# CPU_DIN_mainboard.net
KiCad netlist of a schematic drawn in Altium Designer
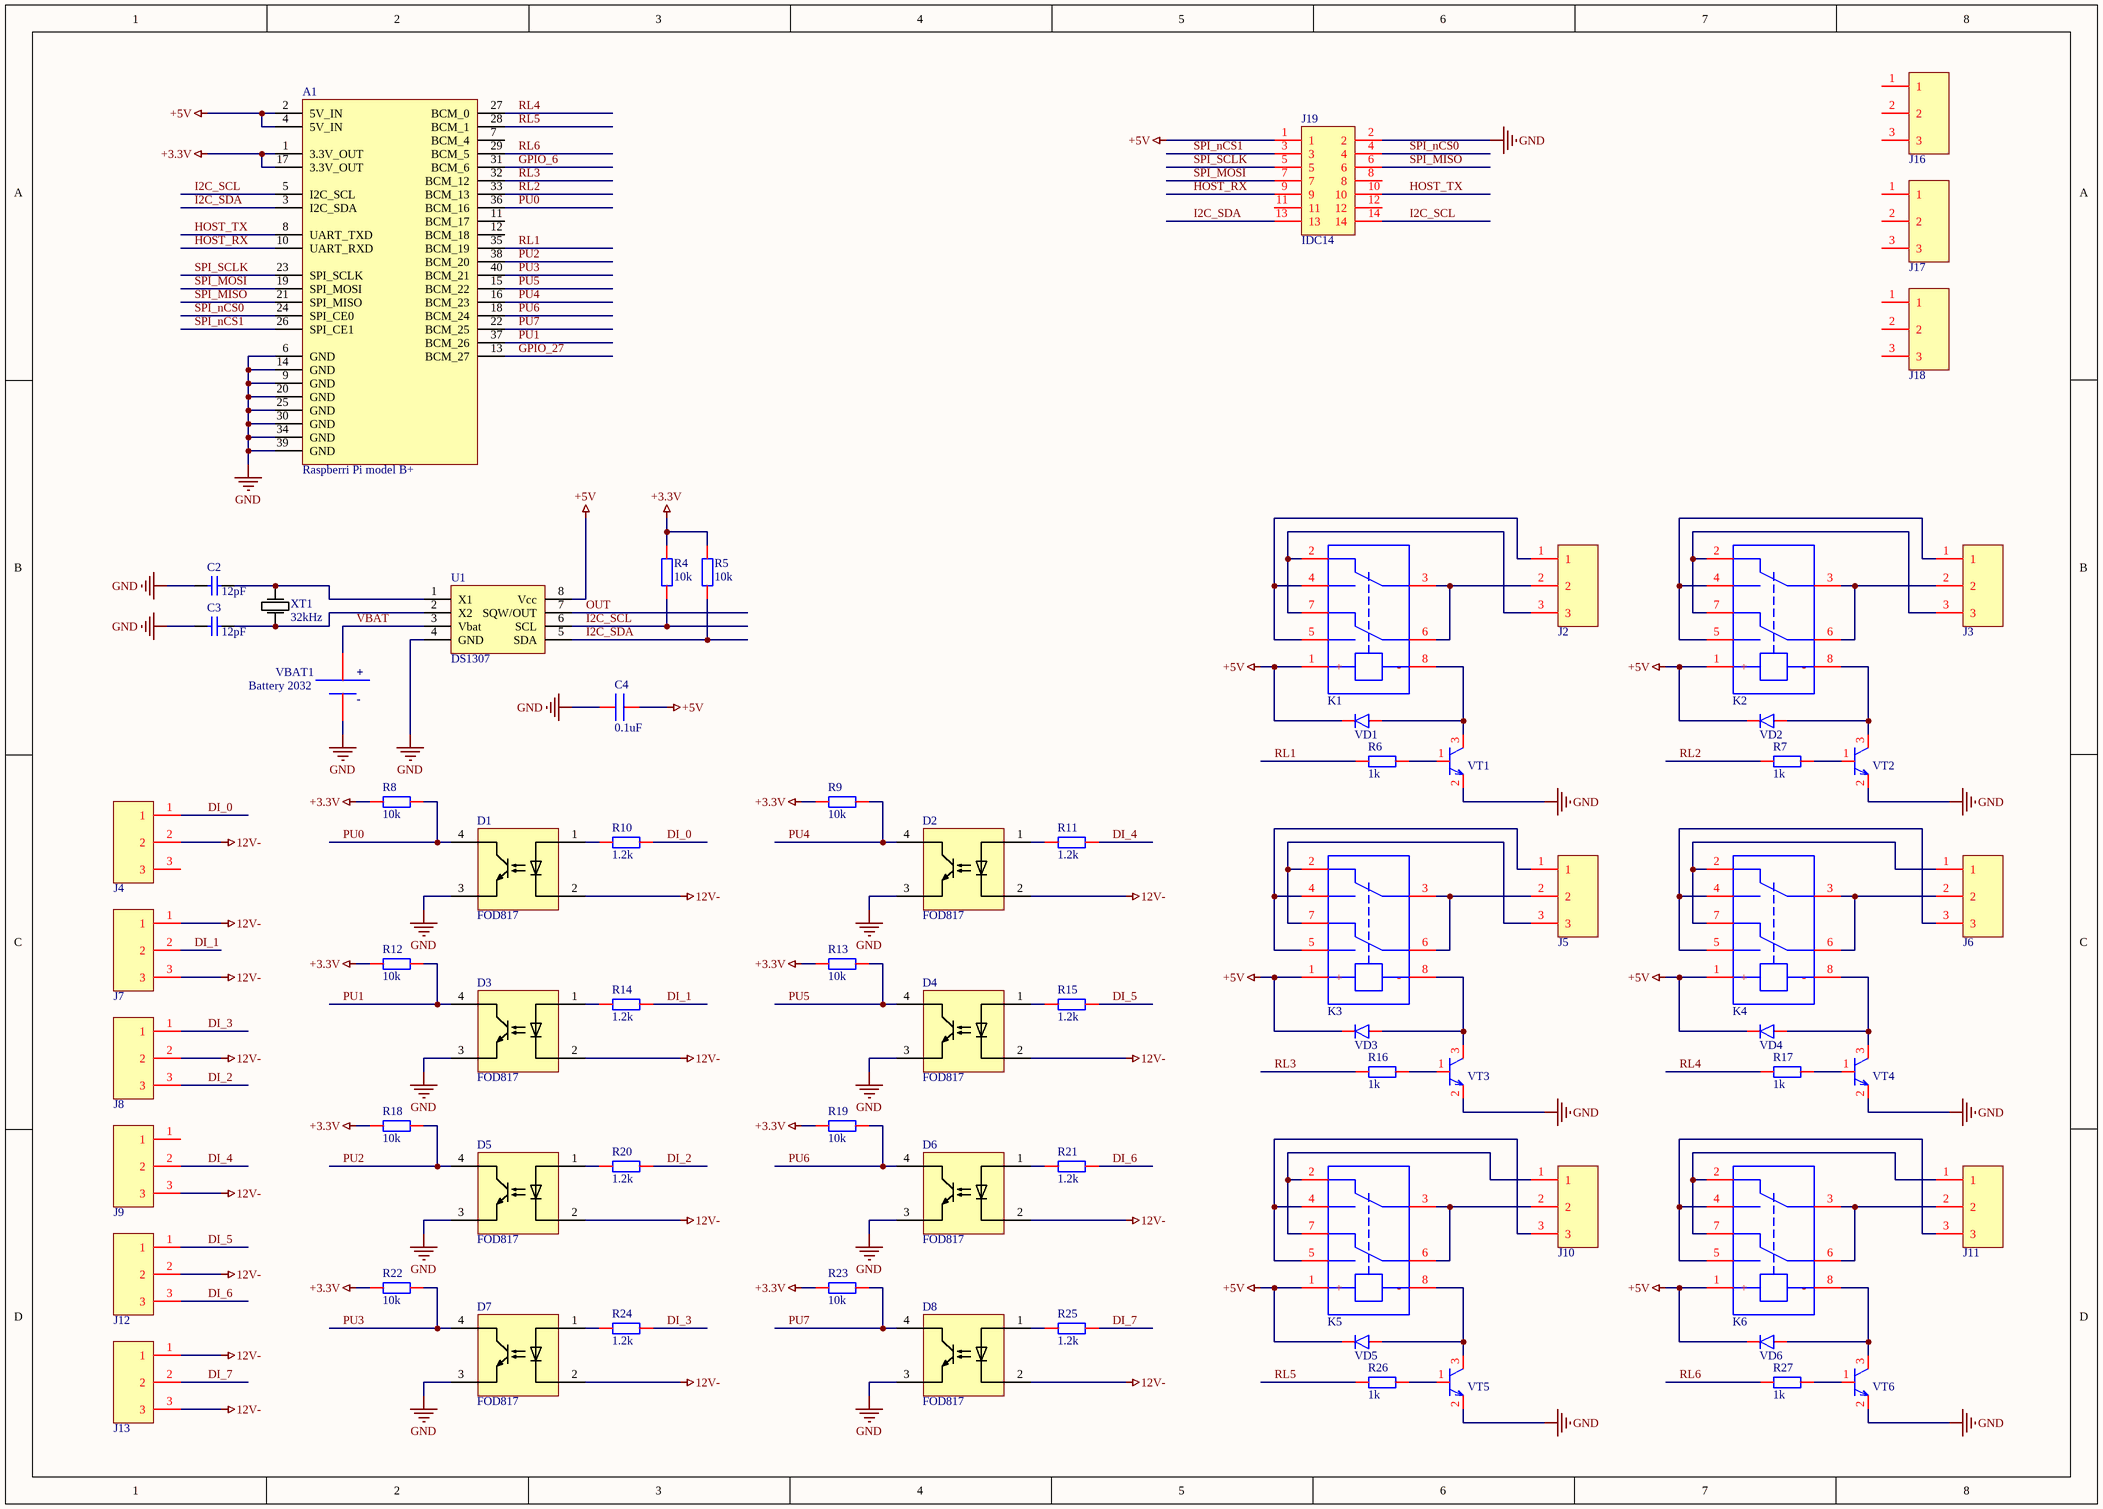
[diagram p0: CPU_DIN_mainboard.SchDoc]

(export (version "E")
  (design (tool "Eeschema 10.0.6"))
  (components
    (comp (ref "A1")
      (value "Raspberri Pi model B+")
      (footprint "PBD-40")
      (fields (field (name "PARTNUM") "PBD-40"))
      (libsource (lib "Lib_001") (part "RPi_Bplus"))
    )
    (comp (ref "C2") (value "12pF") (footprint "C0805") (libsource (lib "") (part "CAP_SMD_1")))
    (comp (ref "C3") (value "12pF") (footprint "C0805") (libsource (lib "") (part "CAP_SMD_1")))
    (comp (ref "C4") (value "0.1uF") (footprint "C0805") (libsource (lib "Lib_001") (part "CAP_SMD")))
    (comp (ref "D1")
      (value "FOD817")
      (footprint "DIP4_300mil_SMD")
      (fields (field (name "PARTNUM") "FOD817ASD"))
      (libsource (lib "Lib_001") (part "FOD817"))
    )
    (comp (ref "D2")
      (value "FOD817")
      (footprint "DIP4_300mil_SMD")
      (fields (field (name "PARTNUM") "FOD817ASD"))
      (libsource (lib "Lib_001") (part "FOD817"))
    )
    (comp (ref "D3")
      (value "FOD817")
      (footprint "DIP4_300mil_SMD")
      (fields (field (name "PARTNUM") "FOD817ASD"))
      (libsource (lib "Lib_001") (part "FOD817"))
    )
    (comp (ref "D4")
      (value "FOD817")
      (footprint "DIP4_300mil_SMD")
      (fields (field (name "PARTNUM") "FOD817ASD"))
      (libsource (lib "Lib_001") (part "FOD817"))
    )
    (comp (ref "D5")
      (value "FOD817")
      (footprint "DIP4_300mil_SMD")
      (fields (field (name "PARTNUM") "FOD817ASD"))
      (libsource (lib "Lib_001") (part "FOD817"))
    )
    (comp (ref "D6")
      (value "FOD817")
      (footprint "DIP4_300mil_SMD")
      (fields (field (name "PARTNUM") "FOD817ASD"))
      (libsource (lib "Lib_001") (part "FOD817"))
    )
    (comp (ref "D7")
      (value "FOD817")
      (footprint "DIP4_300mil_SMD")
      (fields (field (name "PARTNUM") "FOD817ASD"))
      (libsource (lib "Lib_001") (part "FOD817"))
    )
    (comp (ref "D8")
      (value "FOD817")
      (footprint "DIP4_300mil_SMD")
      (fields (field (name "PARTNUM") "FOD817ASD"))
      (libsource (lib "Lib_001") (part "FOD817"))
    )
    (comp (ref "J2")
      (value "Terminal block TB-3")
      (footprint "TB-3_ser370")
      (libsource (lib "Lib_001") (part "TB-3"))
    )
    (comp (ref "J3")
      (value "Terminal block TB-3")
      (footprint "TB-3_ser370")
      (libsource (lib "Lib_001") (part "TB-3"))
    )
    (comp (ref "J4")
      (value "Terminal block TB-3")
      (footprint "TB-3_ser370")
      (libsource (lib "") (part "TB-3_1"))
    )
    (comp (ref "J5")
      (value "Terminal block TB-3")
      (footprint "TB-3_ser370")
      (libsource (lib "Lib_001") (part "TB-3"))
    )
    (comp (ref "J6")
      (value "Terminal block TB-3")
      (footprint "TB-3_ser370")
      (libsource (lib "Lib_001") (part "TB-3"))
    )
    (comp (ref "J7")
      (value "Terminal block TB-3")
      (footprint "TB-3_ser370")
      (libsource (lib "") (part "TB-3_1"))
    )
    (comp (ref "J8")
      (value "Terminal block TB-3")
      (footprint "TB-3_ser370")
      (libsource (lib "") (part "TB-3_1"))
    )
    (comp (ref "J9")
      (value "Terminal block TB-3")
      (footprint "TB-3_ser370")
      (libsource (lib "") (part "TB-3_1"))
    )
    (comp (ref "J10")
      (value "Terminal block TB-3")
      (footprint "TB-3_ser370")
      (libsource (lib "Lib_001") (part "TB-3"))
    )
    (comp (ref "J11")
      (value "Terminal block TB-3")
      (footprint "TB-3_ser370")
      (libsource (lib "Lib_001") (part "TB-3"))
    )
    (comp (ref "J12")
      (value "Terminal block TB-3")
      (footprint "TB-3_ser370")
      (libsource (lib "") (part "TB-3_1"))
    )
    (comp (ref "J13")
      (value "Terminal block TB-3")
      (footprint "TB-3_ser370")
      (libsource (lib "") (part "TB-3_1"))
    )
    (comp (ref "J16")
      (value "Terminal block TB-3")
      (footprint "TB-3_ser370")
      (libsource (lib "Lib_001") (part "TB-3"))
    )
    (comp (ref "J17")
      (value "Terminal block TB-3")
      (footprint "TB-3_ser370")
      (libsource (lib "Lib_001") (part "TB-3"))
    )
    (comp (ref "J18")
      (value "Terminal block TB-3")
      (footprint "TB-3_ser370")
      (libsource (lib "Lib_001") (part "TB-3"))
    )
    (comp (ref "J19") (value "IDC14") (footprint "IDC14") (libsource (lib "Lib_001") (part "IDC14")))
    (comp (ref "K1") (value "IM03GR") (footprint "TYCO_2C") (libsource (lib "Lib_001") (part "IM06GR")))
    (comp (ref "K2") (value "IM03GR") (footprint "TYCO_2C") (libsource (lib "Lib_001") (part "IM06GR")))
    (comp (ref "K3") (value "IM03GR") (footprint "TYCO_2C") (libsource (lib "Lib_001") (part "IM06GR")))
    (comp (ref "K4") (value "IM03GR") (footprint "TYCO_2C") (libsource (lib "Lib_001") (part "IM06GR")))
    (comp (ref "K5") (value "IM03GR") (footprint "TYCO_2C") (libsource (lib "Lib_001") (part "IM06GR")))
    (comp (ref "K6") (value "IM03GR") (footprint "TYCO_2C") (libsource (lib "Lib_001") (part "IM06GR")))
    (comp (ref "R4") (value "10k") (footprint "R0805") (libsource (lib "Lib_001") (part "RES_SMD")))
    (comp (ref "R5") (value "10k") (footprint "R0805") (libsource (lib "Lib_001") (part "RES_SMD")))
    (comp (ref "R6") (value "1k") (footprint "R0805") (libsource (lib "Lib_001") (part "RES_SMD")))
    (comp (ref "R7") (value "1k") (footprint "R0805") (libsource (lib "Lib_001") (part "RES_SMD")))
    (comp (ref "R8") (value "10k") (footprint "R0805") (libsource (lib "Lib_001") (part "RES_SMD")))
    (comp (ref "R9") (value "10k") (footprint "R0805") (libsource (lib "Lib_001") (part "RES_SMD")))
    (comp (ref "R10") (value "1.2k") (footprint "R0805") (libsource (lib "Lib_001") (part "RES_SMD")))
    (comp (ref "R11") (value "1.2k") (footprint "R0805") (libsource (lib "Lib_001") (part "RES_SMD")))
    (comp (ref "R12") (value "10k") (footprint "R0805") (libsource (lib "Lib_001") (part "RES_SMD")))
    (comp (ref "R13") (value "10k") (footprint "R0805") (libsource (lib "Lib_001") (part "RES_SMD")))
    (comp (ref "R14") (value "1.2k") (footprint "R0805") (libsource (lib "Lib_001") (part "RES_SMD")))
    (comp (ref "R15") (value "1.2k") (footprint "R0805") (libsource (lib "Lib_001") (part "RES_SMD")))
    (comp (ref "R16") (value "1k") (footprint "R0805") (libsource (lib "Lib_001") (part "RES_SMD")))
    (comp (ref "R17") (value "1k") (footprint "R0805") (libsource (lib "Lib_001") (part "RES_SMD")))
    (comp (ref "R18") (value "10k") (footprint "R0805") (libsource (lib "Lib_001") (part "RES_SMD")))
    (comp (ref "R19") (value "10k") (footprint "R0805") (libsource (lib "Lib_001") (part "RES_SMD")))
    (comp (ref "R20") (value "1.2k") (footprint "R0805") (libsource (lib "Lib_001") (part "RES_SMD")))
    (comp (ref "R21") (value "1.2k") (footprint "R0805") (libsource (lib "Lib_001") (part "RES_SMD")))
    (comp (ref "R22") (value "10k") (footprint "R0805") (libsource (lib "Lib_001") (part "RES_SMD")))
    (comp (ref "R23") (value "10k") (footprint "R0805") (libsource (lib "Lib_001") (part "RES_SMD")))
    (comp (ref "R24") (value "1.2k") (footprint "R0805") (libsource (lib "Lib_001") (part "RES_SMD")))
    (comp (ref "R25") (value "1.2k") (footprint "R0805") (libsource (lib "Lib_001") (part "RES_SMD")))
    (comp (ref "R26") (value "1k") (footprint "R0805") (libsource (lib "Lib_001") (part "RES_SMD")))
    (comp (ref "R27") (value "1k") (footprint "R0805") (libsource (lib "Lib_001") (part "RES_SMD")))
    (comp (ref "U1")
      (value "DS1307")
      (footprint "SO-8_LM358D")
      (fields (field (name "PARTNUM") "DS1307Z+"))
      (libsource (lib "Lib_001") (part "DS1307"))
    )
    (comp (ref "VBAT1")
      (value "Battery 2032")
      (footprint "Battery_CR2032")
      (fields (field (name "PARTNUM") "BAT/HOLD.HU2032-LF"))
      (libsource (lib "Lib_001") (part "BATTERY_2032"))
    )
    (comp (ref "VD1")
      (value "BAV199")
      (footprint "SMA DIOD")
      (fields (field (name "PARTNUM") "VS-15MQ040NTRPBF"))
      (libsource (lib "Lib_001") (part "DIOD"))
    )
    (comp (ref "VD2")
      (value "BAV199")
      (footprint "SMA DIOD")
      (fields (field (name "PARTNUM") "VS-15MQ040NTRPBF"))
      (libsource (lib "Lib_001") (part "DIOD"))
    )
    (comp (ref "VD3")
      (value "BAV199")
      (footprint "SMA DIOD")
      (fields (field (name "PARTNUM") "VS-15MQ040NTRPBF"))
      (libsource (lib "Lib_001") (part "DIOD"))
    )
    (comp (ref "VD4")
      (value "BAV199")
      (footprint "SMA DIOD")
      (fields (field (name "PARTNUM") "VS-15MQ040NTRPBF"))
      (libsource (lib "Lib_001") (part "DIOD"))
    )
    (comp (ref "VD5")
      (value "BAV199")
      (footprint "SMA DIOD")
      (fields (field (name "PARTNUM") "VS-15MQ040NTRPBF"))
      (libsource (lib "Lib_001") (part "DIOD"))
    )
    (comp (ref "VD6")
      (value "BAV199")
      (footprint "SMA DIOD")
      (fields (field (name "PARTNUM") "VS-15MQ040NTRPBF"))
      (libsource (lib "Lib_001") (part "DIOD"))
    )
    (comp (ref "VT1")
      (value "BC817")
      (footprint "SOT23")
      (fields (field (name "PARTNUM") "BC817-16LT1G"))
      (libsource (lib "Lib_001") (part "BC817"))
    )
    (comp (ref "VT2")
      (value "BC817")
      (footprint "SOT23")
      (fields (field (name "PARTNUM") "BC817-16LT1G"))
      (libsource (lib "Lib_001") (part "BC817"))
    )
    (comp (ref "VT3")
      (value "BC817")
      (footprint "SOT23")
      (fields (field (name "PARTNUM") "BC817-16LT1G"))
      (libsource (lib "Lib_001") (part "BC817"))
    )
    (comp (ref "VT4")
      (value "BC817")
      (footprint "SOT23")
      (fields (field (name "PARTNUM") "BC817-16LT1G"))
      (libsource (lib "Lib_001") (part "BC817"))
    )
    (comp (ref "VT5")
      (value "BC817")
      (footprint "SOT23")
      (fields (field (name "PARTNUM") "BC817-16LT1G"))
      (libsource (lib "Lib_001") (part "BC817"))
    )
    (comp (ref "VT6")
      (value "BC817")
      (footprint "SOT23")
      (fields (field (name "PARTNUM") "BC817-16LT1G"))
      (libsource (lib "Lib_001") (part "BC817"))
    )
    (comp (ref "XT1")
      (value "32kHz")
      (footprint "XTAL_d2x6mm")
      (fields (field (name "PARTNUM") "KX-26T 32.768 kHz"))
      (libsource (lib "Lib_001") (part "XTAL"))
    )
  )
  (nets
    (net (code "1") (name "+3.3V") (class "Default")
      (node (ref "A1") (pin "1") (pinfunction "3.3V_OUT_1") (pintype "passive"))
      (node (ref "A1") (pin "17") (pinfunction "3.3V_OUT_17") (pintype "passive"))
      (node (ref "R12") (pin "2") (pinfunction "2_2") (pintype "passive"))
      (node (ref "R13") (pin "2") (pinfunction "2_2") (pintype "passive"))
      (node (ref "R18") (pin "2") (pinfunction "2_2") (pintype "passive"))
      (node (ref "R19") (pin "2") (pinfunction "2_2") (pintype "passive"))
      (node (ref "R22") (pin "2") (pinfunction "2_2") (pintype "passive"))
      (node (ref "R23") (pin "2") (pinfunction "2_2") (pintype "passive"))
      (node (ref "R4") (pin "2") (pinfunction "2_2") (pintype "passive"))
      (node (ref "R5") (pin "2") (pinfunction "2_2") (pintype "passive"))
      (node (ref "R8") (pin "2") (pinfunction "2_2") (pintype "passive"))
      (node (ref "R9") (pin "2") (pinfunction "2_2") (pintype "passive"))
    )
    (net (code "2") (name "+5V") (class "Default")
      (node (ref "A1") (pin "2") (pinfunction "5V_IN_2") (pintype "passive"))
      (node (ref "A1") (pin "4") (pinfunction "5V_IN_4") (pintype "passive"))
      (node (ref "C4") (pin "2") (pinfunction "2_2") (pintype "passive"))
      (node (ref "J19") (pin "1") (pinfunction "1_1") (pintype "passive"))
      (node (ref "K1") (pin "1") (pinfunction "+_1") (pintype "passive"))
      (node (ref "K2") (pin "1") (pinfunction "+_1") (pintype "passive"))
      (node (ref "K3") (pin "1") (pinfunction "+_1") (pintype "passive"))
      (node (ref "K4") (pin "1") (pinfunction "+_1") (pintype "passive"))
      (node (ref "K5") (pin "1") (pinfunction "+_1") (pintype "passive"))
      (node (ref "K6") (pin "1") (pinfunction "+_1") (pintype "passive"))
      (node (ref "U1") (pin "8") (pinfunction "Vcc_8") (pintype "passive"))
      (node (ref "VD1") (pin "K") (pinfunction "K_K") (pintype "passive"))
      (node (ref "VD2") (pin "K") (pinfunction "K_K") (pintype "passive"))
      (node (ref "VD3") (pin "K") (pinfunction "K_K") (pintype "passive"))
      (node (ref "VD4") (pin "K") (pinfunction "K_K") (pintype "passive"))
      (node (ref "VD5") (pin "K") (pinfunction "K_K") (pintype "passive"))
      (node (ref "VD6") (pin "K") (pinfunction "K_K") (pintype "passive"))
    )
    (net (code "3") (name "/DI_0") (class "Default")
      (node (ref "J4") (pin "1") (pinfunction "1_1") (pintype "passive"))
      (node (ref "R10") (pin "1") (pinfunction "1_1") (pintype "passive"))
    )
    (net (code "4") (name "/DI_1") (class "Default")
      (node (ref "J7") (pin "2") (pinfunction "2_2") (pintype "passive"))
      (node (ref "R14") (pin "1") (pinfunction "1_1") (pintype "passive"))
    )
    (net (code "5") (name "/DI_2") (class "Default")
      (node (ref "J8") (pin "3") (pinfunction "3_3") (pintype "passive"))
      (node (ref "R20") (pin "1") (pinfunction "1_1") (pintype "passive"))
    )
    (net (code "6") (name "/DI_3") (class "Default")
      (node (ref "J8") (pin "1") (pinfunction "1_1") (pintype "passive"))
      (node (ref "R24") (pin "1") (pinfunction "1_1") (pintype "passive"))
    )
    (net (code "7") (name "/DI_4") (class "Default")
      (node (ref "J9") (pin "2") (pinfunction "2_2") (pintype "passive"))
      (node (ref "R11") (pin "1") (pinfunction "1_1") (pintype "passive"))
    )
    (net (code "8") (name "/DI_5") (class "Default")
      (node (ref "J12") (pin "1") (pinfunction "1_1") (pintype "passive"))
      (node (ref "R15") (pin "1") (pinfunction "1_1") (pintype "passive"))
    )
    (net (code "9") (name "/DI_6") (class "Default")
      (node (ref "J12") (pin "3") (pinfunction "3_3") (pintype "passive"))
      (node (ref "R21") (pin "1") (pinfunction "1_1") (pintype "passive"))
    )
    (net (code "10") (name "/DI_7") (class "Default")
      (node (ref "J13") (pin "2") (pinfunction "2_2") (pintype "passive"))
      (node (ref "R25") (pin "1") (pinfunction "1_1") (pintype "passive"))
    )
    (net (code "11") (name "/GPIO_6") (class "Default")
      (node (ref "A1") (pin "31") (pinfunction "BCM_6_31") (pintype "passive"))
    )
    (net (code "12") (name "/GPIO_27") (class "Default")
      (node (ref "A1") (pin "13") (pinfunction "BCM_27_13") (pintype "passive"))
    )
    (net (code "13") (name "/HOST_RX") (class "Default")
      (node (ref "A1") (pin "10") (pinfunction "UART_RXD_10") (pintype "passive"))
      (node (ref "J19") (pin "9") (pinfunction "9_9") (pintype "passive"))
    )
    (net (code "14") (name "/HOST_TX") (class "Default")
      (node (ref "A1") (pin "8") (pinfunction "UART_TXD_8") (pintype "passive"))
      (node (ref "J19") (pin "10") (pinfunction "10_10") (pintype "passive"))
    )
    (net (code "15") (name "/I2C_SCL") (class "Default")
      (node (ref "A1") (pin "5") (pinfunction "I2C_SCL_5") (pintype "passive"))
      (node (ref "J19") (pin "14") (pinfunction "14_14") (pintype "passive"))
      (node (ref "R4") (pin "1") (pinfunction "1_1") (pintype "passive"))
      (node (ref "U1") (pin "6") (pinfunction "SCL_6") (pintype "passive"))
    )
    (net (code "16") (name "/I2C_SDA") (class "Default")
      (node (ref "A1") (pin "3") (pinfunction "I2C_SDA_3") (pintype "passive"))
      (node (ref "J19") (pin "13") (pinfunction "13_13") (pintype "passive"))
      (node (ref "R5") (pin "1") (pinfunction "1_1") (pintype "passive"))
      (node (ref "U1") (pin "5") (pinfunction "SDA_5") (pintype "passive"))
    )
    (net (code "17") (name "/OUT") (class "Default")
      (node (ref "U1") (pin "7") (pinfunction "SQW/OUT_7") (pintype "passive"))
    )
    (net (code "18") (name "/PU0") (class "Default")
      (node (ref "A1") (pin "36") (pinfunction "BCM_16_36") (pintype "passive"))
      (node (ref "D1") (pin "4") (pinfunction "4_4") (pintype "passive"))
      (node (ref "R8") (pin "1") (pinfunction "1_1") (pintype "passive"))
    )
    (net (code "19") (name "/PU1") (class "Default")
      (node (ref "A1") (pin "37") (pinfunction "BCM_26_37") (pintype "passive"))
      (node (ref "D3") (pin "4") (pinfunction "4_4") (pintype "passive"))
      (node (ref "R12") (pin "1") (pinfunction "1_1") (pintype "passive"))
    )
    (net (code "20") (name "/PU2") (class "Default")
      (node (ref "A1") (pin "38") (pinfunction "BCM_20_38") (pintype "passive"))
      (node (ref "D5") (pin "4") (pinfunction "4_4") (pintype "passive"))
      (node (ref "R18") (pin "1") (pinfunction "1_1") (pintype "passive"))
    )
    (net (code "21") (name "/PU3") (class "Default")
      (node (ref "A1") (pin "40") (pinfunction "BCM_21_40") (pintype "passive"))
      (node (ref "D7") (pin "4") (pinfunction "4_4") (pintype "passive"))
      (node (ref "R22") (pin "1") (pinfunction "1_1") (pintype "passive"))
    )
    (net (code "22") (name "/PU4") (class "Default")
      (node (ref "A1") (pin "16") (pinfunction "BCM_23_16") (pintype "passive"))
      (node (ref "D2") (pin "4") (pinfunction "4_4") (pintype "passive"))
      (node (ref "R9") (pin "1") (pinfunction "1_1") (pintype "passive"))
    )
    (net (code "23") (name "/PU5") (class "Default")
      (node (ref "A1") (pin "15") (pinfunction "BCM_22_15") (pintype "passive"))
      (node (ref "D4") (pin "4") (pinfunction "4_4") (pintype "passive"))
      (node (ref "R13") (pin "1") (pinfunction "1_1") (pintype "passive"))
    )
    (net (code "24") (name "/PU6") (class "Default")
      (node (ref "A1") (pin "18") (pinfunction "BCM_24_18") (pintype "passive"))
      (node (ref "D6") (pin "4") (pinfunction "4_4") (pintype "passive"))
      (node (ref "R19") (pin "1") (pinfunction "1_1") (pintype "passive"))
    )
    (net (code "25") (name "/PU7") (class "Default")
      (node (ref "A1") (pin "22") (pinfunction "BCM_25_22") (pintype "passive"))
      (node (ref "D8") (pin "4") (pinfunction "4_4") (pintype "passive"))
      (node (ref "R23") (pin "1") (pinfunction "1_1") (pintype "passive"))
    )
    (net (code "26") (name "/RL1") (class "Default")
      (node (ref "A1") (pin "35") (pinfunction "BCM_19_35") (pintype "passive"))
      (node (ref "R6") (pin "2") (pinfunction "2_2") (pintype "passive"))
    )
    (net (code "27") (name "/RL2") (class "Default")
      (node (ref "A1") (pin "33") (pinfunction "BCM_13_33") (pintype "passive"))
      (node (ref "R7") (pin "2") (pinfunction "2_2") (pintype "passive"))
    )
    (net (code "28") (name "/RL3") (class "Default")
      (node (ref "A1") (pin "32") (pinfunction "BCM_12_32") (pintype "passive"))
      (node (ref "R16") (pin "2") (pinfunction "2_2") (pintype "passive"))
    )
    (net (code "29") (name "/RL4") (class "Default")
      (node (ref "A1") (pin "27") (pinfunction "BCM_0_27") (pintype "passive"))
      (node (ref "R17") (pin "2") (pinfunction "2_2") (pintype "passive"))
    )
    (net (code "30") (name "/RL5") (class "Default")
      (node (ref "A1") (pin "28") (pinfunction "BCM_1_28") (pintype "passive"))
      (node (ref "R26") (pin "2") (pinfunction "2_2") (pintype "passive"))
    )
    (net (code "31") (name "/RL6") (class "Default")
      (node (ref "A1") (pin "29") (pinfunction "BCM_5_29") (pintype "passive"))
      (node (ref "R27") (pin "2") (pinfunction "2_2") (pintype "passive"))
    )
    (net (code "32") (name "/SPI_MISO") (class "Default")
      (node (ref "A1") (pin "21") (pinfunction "SPI_MISO_21") (pintype "passive"))
      (node (ref "J19") (pin "6") (pinfunction "6_6") (pintype "passive"))
    )
    (net (code "33") (name "/SPI_MOSI") (class "Default")
      (node (ref "A1") (pin "19") (pinfunction "SPI_MOSI_19") (pintype "passive"))
      (node (ref "J19") (pin "7") (pinfunction "7_7") (pintype "passive"))
    )
    (net (code "34") (name "/SPI_SCLK") (class "Default")
      (node (ref "A1") (pin "23") (pinfunction "SPI_SCLK_23") (pintype "passive"))
      (node (ref "J19") (pin "5") (pinfunction "5_5") (pintype "passive"))
    )
    (net (code "35") (name "/SPI_nCS0") (class "Default")
      (node (ref "A1") (pin "24") (pinfunction "SPI_CE0_24") (pintype "passive"))
      (node (ref "J19") (pin "4") (pinfunction "4_4") (pintype "passive"))
    )
    (net (code "36") (name "/SPI_nCS1") (class "Default")
      (node (ref "A1") (pin "26") (pinfunction "SPI_CE1_26") (pintype "passive"))
      (node (ref "J19") (pin "3") (pinfunction "3_3") (pintype "passive"))
    )
    (net (code "37") (name "/VBAT") (class "Default")
      (node (ref "U1") (pin "3") (pinfunction "Vbat_3") (pintype "passive"))
      (node (ref "VBAT1") (pin "P") (pinfunction "+_P") (pintype "passive"))
    )
    (net (code "38") (name "12V-") (class "Default")
      (node (ref "D1") (pin "2") (pinfunction "2_2") (pintype "passive"))
      (node (ref "D2") (pin "2") (pinfunction "2_2") (pintype "passive"))
      (node (ref "D3") (pin "2") (pinfunction "2_2") (pintype "passive"))
      (node (ref "D4") (pin "2") (pinfunction "2_2") (pintype "passive"))
      (node (ref "D5") (pin "2") (pinfunction "2_2") (pintype "passive"))
      (node (ref "D6") (pin "2") (pinfunction "2_2") (pintype "passive"))
      (node (ref "D7") (pin "2") (pinfunction "2_2") (pintype "passive"))
      (node (ref "D8") (pin "2") (pinfunction "2_2") (pintype "passive"))
      (node (ref "J12") (pin "2") (pinfunction "2_2") (pintype "passive"))
      (node (ref "J13") (pin "1") (pinfunction "1_1") (pintype "passive"))
      (node (ref "J13") (pin "3") (pinfunction "3_3") (pintype "passive"))
      (node (ref "J4") (pin "2") (pinfunction "2_2") (pintype "passive"))
      (node (ref "J7") (pin "1") (pinfunction "1_1") (pintype "passive"))
      (node (ref "J7") (pin "3") (pinfunction "3_3") (pintype "passive"))
      (node (ref "J8") (pin "2") (pinfunction "2_2") (pintype "passive"))
      (node (ref "J9") (pin "3") (pinfunction "3_3") (pintype "passive"))
    )
    (net (code "39") (name "GND") (class "Default")
      (node (ref "A1") (pin "14") (pinfunction "GND_14") (pintype "passive"))
      (node (ref "A1") (pin "20") (pinfunction "GND_20") (pintype "passive"))
      (node (ref "A1") (pin "25") (pinfunction "GND_25") (pintype "passive"))
      (node (ref "A1") (pin "30") (pinfunction "GND_30") (pintype "passive"))
      (node (ref "A1") (pin "34") (pinfunction "GND_34") (pintype "passive"))
      (node (ref "A1") (pin "39") (pinfunction "GND_39") (pintype "passive"))
      (node (ref "A1") (pin "6") (pinfunction "GND_6") (pintype "passive"))
      (node (ref "A1") (pin "9") (pinfunction "GND_9") (pintype "passive"))
      (node (ref "C2") (pin "2") (pinfunction "2_2") (pintype "passive"))
      (node (ref "C3") (pin "2") (pinfunction "2_2") (pintype "passive"))
      (node (ref "C4") (pin "1") (pinfunction "1_1") (pintype "passive"))
      (node (ref "D1") (pin "3") (pinfunction "3_3") (pintype "passive"))
      (node (ref "D2") (pin "3") (pinfunction "3_3") (pintype "passive"))
      (node (ref "D3") (pin "3") (pinfunction "3_3") (pintype "passive"))
      (node (ref "D4") (pin "3") (pinfunction "3_3") (pintype "passive"))
      (node (ref "D5") (pin "3") (pinfunction "3_3") (pintype "passive"))
      (node (ref "D6") (pin "3") (pinfunction "3_3") (pintype "passive"))
      (node (ref "D7") (pin "3") (pinfunction "3_3") (pintype "passive"))
      (node (ref "D8") (pin "3") (pinfunction "3_3") (pintype "passive"))
      (node (ref "J19") (pin "2") (pinfunction "2_2") (pintype "passive"))
      (node (ref "U1") (pin "4") (pinfunction "GND_4") (pintype "passive"))
      (node (ref "VBAT1") (pin "N") (pinfunction "-_N") (pintype "passive"))
      (node (ref "VT1") (pin "2") (pinfunction "E_2") (pintype "passive"))
      (node (ref "VT2") (pin "2") (pinfunction "E_2") (pintype "passive"))
      (node (ref "VT3") (pin "2") (pinfunction "E_2") (pintype "passive"))
      (node (ref "VT4") (pin "2") (pinfunction "E_2") (pintype "passive"))
      (node (ref "VT5") (pin "2") (pinfunction "E_2") (pintype "passive"))
      (node (ref "VT6") (pin "2") (pinfunction "E_2") (pintype "passive"))
    )
    (net (code "40") (name "Net-(D1-Pad1)") (class "Default")
      (node (ref "D1") (pin "1") (pinfunction "1_1") (pintype "passive"))
      (node (ref "R10") (pin "2") (pinfunction "2_2") (pintype "passive"))
    )
    (net (code "41") (name "Net-(D2-Pad1)") (class "Default")
      (node (ref "D2") (pin "1") (pinfunction "1_1") (pintype "passive"))
      (node (ref "R11") (pin "2") (pinfunction "2_2") (pintype "passive"))
    )
    (net (code "42") (name "Net-(D3-Pad1)") (class "Default")
      (node (ref "D3") (pin "1") (pinfunction "1_1") (pintype "passive"))
      (node (ref "R14") (pin "2") (pinfunction "2_2") (pintype "passive"))
    )
    (net (code "43") (name "Net-(D4-Pad1)") (class "Default")
      (node (ref "D4") (pin "1") (pinfunction "1_1") (pintype "passive"))
      (node (ref "R15") (pin "2") (pinfunction "2_2") (pintype "passive"))
    )
    (net (code "44") (name "Net-(D5-Pad1)") (class "Default")
      (node (ref "D5") (pin "1") (pinfunction "1_1") (pintype "passive"))
      (node (ref "R20") (pin "2") (pinfunction "2_2") (pintype "passive"))
    )
    (net (code "45") (name "Net-(D6-Pad1)") (class "Default")
      (node (ref "D6") (pin "1") (pinfunction "1_1") (pintype "passive"))
      (node (ref "R21") (pin "2") (pinfunction "2_2") (pintype "passive"))
    )
    (net (code "46") (name "Net-(D7-Pad1)") (class "Default")
      (node (ref "D7") (pin "1") (pinfunction "1_1") (pintype "passive"))
      (node (ref "R24") (pin "2") (pinfunction "2_2") (pintype "passive"))
    )
    (net (code "47") (name "Net-(D8-Pad1)") (class "Default")
      (node (ref "D8") (pin "1") (pinfunction "1_1") (pintype "passive"))
      (node (ref "R25") (pin "2") (pinfunction "2_2") (pintype "passive"))
    )
    (net (code "48") (name "Net-(J2-Pad1)") (class "Default")
      (node (ref "J2") (pin "1") (pinfunction "1_1") (pintype "passive"))
      (node (ref "K1") (pin "4") (pinfunction "4_4") (pintype "passive"))
      (node (ref "K1") (pin "5") (pinfunction "5_5") (pintype "passive"))
    )
    (net (code "49") (name "Net-(J2-Pad3)") (class "Default")
      (node (ref "J2") (pin "3") (pinfunction "3_3") (pintype "passive"))
      (node (ref "K1") (pin "2") (pinfunction "2_2") (pintype "passive"))
      (node (ref "K1") (pin "7") (pinfunction "7_7") (pintype "passive"))
    )
    (net (code "50") (name "Net-(J3-Pad1)") (class "Default")
      (node (ref "J3") (pin "1") (pinfunction "1_1") (pintype "passive"))
      (node (ref "K2") (pin "4") (pinfunction "4_4") (pintype "passive"))
      (node (ref "K2") (pin "5") (pinfunction "5_5") (pintype "passive"))
    )
    (net (code "51") (name "Net-(J3-Pad3)") (class "Default")
      (node (ref "J3") (pin "3") (pinfunction "3_3") (pintype "passive"))
      (node (ref "K2") (pin "2") (pinfunction "2_2") (pintype "passive"))
      (node (ref "K2") (pin "7") (pinfunction "7_7") (pintype "passive"))
    )
    (net (code "52") (name "Net-(J5-Pad1)") (class "Default")
      (node (ref "J5") (pin "1") (pinfunction "1_1") (pintype "passive"))
      (node (ref "K3") (pin "4") (pinfunction "4_4") (pintype "passive"))
      (node (ref "K3") (pin "5") (pinfunction "5_5") (pintype "passive"))
    )
    (net (code "53") (name "Net-(J5-Pad3)") (class "Default")
      (node (ref "J5") (pin "3") (pinfunction "3_3") (pintype "passive"))
      (node (ref "K3") (pin "2") (pinfunction "2_2") (pintype "passive"))
      (node (ref "K3") (pin "7") (pinfunction "7_7") (pintype "passive"))
    )
    (net (code "54") (name "Net-(J6-Pad1)") (class "Default")
      (node (ref "J6") (pin "1") (pinfunction "1_1") (pintype "passive"))
      (node (ref "K4") (pin "2") (pinfunction "2_2") (pintype "passive"))
      (node (ref "K4") (pin "7") (pinfunction "7_7") (pintype "passive"))
    )
    (net (code "55") (name "Net-(J6-Pad3)") (class "Default")
      (node (ref "J6") (pin "3") (pinfunction "3_3") (pintype "passive"))
      (node (ref "K4") (pin "4") (pinfunction "4_4") (pintype "passive"))
      (node (ref "K4") (pin "5") (pinfunction "5_5") (pintype "passive"))
    )
    (net (code "56") (name "Net-(J10-Pad1)") (class "Default")
      (node (ref "J10") (pin "1") (pinfunction "1_1") (pintype "passive"))
      (node (ref "K5") (pin "2") (pinfunction "2_2") (pintype "passive"))
      (node (ref "K5") (pin "7") (pinfunction "7_7") (pintype "passive"))
    )
    (net (code "57") (name "Net-(J10-Pad3)") (class "Default")
      (node (ref "J10") (pin "3") (pinfunction "3_3") (pintype "passive"))
      (node (ref "K5") (pin "4") (pinfunction "4_4") (pintype "passive"))
      (node (ref "K5") (pin "5") (pinfunction "5_5") (pintype "passive"))
    )
    (net (code "58") (name "Net-(J11-Pad1)") (class "Default")
      (node (ref "J11") (pin "1") (pinfunction "1_1") (pintype "passive"))
      (node (ref "K6") (pin "2") (pinfunction "2_2") (pintype "passive"))
      (node (ref "K6") (pin "7") (pinfunction "7_7") (pintype "passive"))
    )
    (net (code "59") (name "Net-(J11-Pad3)") (class "Default")
      (node (ref "J11") (pin "3") (pinfunction "3_3") (pintype "passive"))
      (node (ref "K6") (pin "4") (pinfunction "4_4") (pintype "passive"))
      (node (ref "K6") (pin "5") (pinfunction "5_5") (pintype "passive"))
    )
    (net (code "60") (name "Net-(K1--)") (class "Default")
      (node (ref "K1") (pin "8") (pinfunction "-_8") (pintype "passive"))
      (node (ref "VD1") (pin "A") (pinfunction "A_A") (pintype "passive"))
      (node (ref "VT1") (pin "3") (pinfunction "C_3") (pintype "passive"))
    )
    (net (code "61") (name "Net-(K1-1C)") (class "Default")
      (node (ref "J2") (pin "2") (pinfunction "2_2") (pintype "passive"))
      (node (ref "K1") (pin "3") (pinfunction "1C_3") (pintype "passive"))
      (node (ref "K1") (pin "6") (pinfunction "2C_6") (pintype "passive"))
    )
    (net (code "62") (name "Net-(K2--)") (class "Default")
      (node (ref "K2") (pin "8") (pinfunction "-_8") (pintype "passive"))
      (node (ref "VD2") (pin "A") (pinfunction "A_A") (pintype "passive"))
      (node (ref "VT2") (pin "3") (pinfunction "C_3") (pintype "passive"))
    )
    (net (code "63") (name "Net-(K2-1C)") (class "Default")
      (node (ref "J3") (pin "2") (pinfunction "2_2") (pintype "passive"))
      (node (ref "K2") (pin "3") (pinfunction "1C_3") (pintype "passive"))
      (node (ref "K2") (pin "6") (pinfunction "2C_6") (pintype "passive"))
    )
    (net (code "64") (name "Net-(K3--)") (class "Default")
      (node (ref "K3") (pin "8") (pinfunction "-_8") (pintype "passive"))
      (node (ref "VD3") (pin "A") (pinfunction "A_A") (pintype "passive"))
      (node (ref "VT3") (pin "3") (pinfunction "C_3") (pintype "passive"))
    )
    (net (code "65") (name "Net-(K3-1C)") (class "Default")
      (node (ref "J5") (pin "2") (pinfunction "2_2") (pintype "passive"))
      (node (ref "K3") (pin "3") (pinfunction "1C_3") (pintype "passive"))
      (node (ref "K3") (pin "6") (pinfunction "2C_6") (pintype "passive"))
    )
    (net (code "66") (name "Net-(K4--)") (class "Default")
      (node (ref "K4") (pin "8") (pinfunction "-_8") (pintype "passive"))
      (node (ref "VD4") (pin "A") (pinfunction "A_A") (pintype "passive"))
      (node (ref "VT4") (pin "3") (pinfunction "C_3") (pintype "passive"))
    )
    (net (code "67") (name "Net-(K4-1C)") (class "Default")
      (node (ref "J6") (pin "2") (pinfunction "2_2") (pintype "passive"))
      (node (ref "K4") (pin "3") (pinfunction "1C_3") (pintype "passive"))
      (node (ref "K4") (pin "6") (pinfunction "2C_6") (pintype "passive"))
    )
    (net (code "68") (name "Net-(K5--)") (class "Default")
      (node (ref "K5") (pin "8") (pinfunction "-_8") (pintype "passive"))
      (node (ref "VD5") (pin "A") (pinfunction "A_A") (pintype "passive"))
      (node (ref "VT5") (pin "3") (pinfunction "C_3") (pintype "passive"))
    )
    (net (code "69") (name "Net-(K5-1C)") (class "Default")
      (node (ref "J10") (pin "2") (pinfunction "2_2") (pintype "passive"))
      (node (ref "K5") (pin "3") (pinfunction "1C_3") (pintype "passive"))
      (node (ref "K5") (pin "6") (pinfunction "2C_6") (pintype "passive"))
    )
    (net (code "70") (name "Net-(K6--)") (class "Default")
      (node (ref "K6") (pin "8") (pinfunction "-_8") (pintype "passive"))
      (node (ref "VD6") (pin "A") (pinfunction "A_A") (pintype "passive"))
      (node (ref "VT6") (pin "3") (pinfunction "C_3") (pintype "passive"))
    )
    (net (code "71") (name "Net-(K6-1C)") (class "Default")
      (node (ref "J11") (pin "2") (pinfunction "2_2") (pintype "passive"))
      (node (ref "K6") (pin "3") (pinfunction "1C_3") (pintype "passive"))
      (node (ref "K6") (pin "6") (pinfunction "2C_6") (pintype "passive"))
    )
    (net (code "72") (name "Net-(U1-X1)") (class "Default")
      (node (ref "C2") (pin "1") (pinfunction "1_1") (pintype "passive"))
      (node (ref "U1") (pin "1") (pinfunction "X1_1") (pintype "passive"))
      (node (ref "XT1") (pin "2") (pinfunction "2_2") (pintype "passive"))
    )
    (net (code "73") (name "Net-(U1-X2)") (class "Default")
      (node (ref "C3") (pin "1") (pinfunction "1_1") (pintype "passive"))
      (node (ref "U1") (pin "2") (pinfunction "X2_2") (pintype "passive"))
      (node (ref "XT1") (pin "1") (pinfunction "1_1") (pintype "passive"))
    )
    (net (code "74") (name "Net-(VT1-B)") (class "Default")
      (node (ref "R6") (pin "1") (pinfunction "1_1") (pintype "passive"))
      (node (ref "VT1") (pin "1") (pinfunction "B_1") (pintype "passive"))
    )
    (net (code "75") (name "Net-(VT2-B)") (class "Default")
      (node (ref "R7") (pin "1") (pinfunction "1_1") (pintype "passive"))
      (node (ref "VT2") (pin "1") (pinfunction "B_1") (pintype "passive"))
    )
    (net (code "76") (name "Net-(VT3-B)") (class "Default")
      (node (ref "R16") (pin "1") (pinfunction "1_1") (pintype "passive"))
      (node (ref "VT3") (pin "1") (pinfunction "B_1") (pintype "passive"))
    )
    (net (code "77") (name "Net-(VT4-B)") (class "Default")
      (node (ref "R17") (pin "1") (pinfunction "1_1") (pintype "passive"))
      (node (ref "VT4") (pin "1") (pinfunction "B_1") (pintype "passive"))
    )
    (net (code "78") (name "Net-(VT5-B)") (class "Default")
      (node (ref "R26") (pin "1") (pinfunction "1_1") (pintype "passive"))
      (node (ref "VT5") (pin "1") (pinfunction "B_1") (pintype "passive"))
    )
    (net (code "79") (name "Net-(VT6-B)") (class "Default")
      (node (ref "R27") (pin "1") (pinfunction "1_1") (pintype "passive"))
      (node (ref "VT6") (pin "1") (pinfunction "B_1") (pintype "passive"))
    )
    (net (code "80") (name "unconnected-(A1-BCM_4-Pad7)") (class "Default")
      (node (ref "A1") (pin "7") (pinfunction "BCM_4_7") (pintype "passive"))
    )
    (net (code "81") (name "unconnected-(A1-BCM_17-Pad11)") (class "Default")
      (node (ref "A1") (pin "11") (pinfunction "BCM_17_11") (pintype "passive"))
    )
    (net (code "82") (name "unconnected-(A1-BCM_18-Pad12)") (class "Default")
      (node (ref "A1") (pin "12") (pinfunction "BCM_18_12") (pintype "passive"))
    )
    (net (code "83") (name "unconnected-(J4-Pad3)") (class "Default")
      (node (ref "J4") (pin "3") (pinfunction "3_3") (pintype "passive"))
    )
    (net (code "84") (name "unconnected-(J9-Pad1)") (class "Default")
      (node (ref "J9") (pin "1") (pinfunction "1_1") (pintype "passive"))
    )
    (net (code "85") (name "unconnected-(J16-Pad1)") (class "Default")
      (node (ref "J16") (pin "1") (pinfunction "1_1") (pintype "passive"))
    )
    (net (code "86") (name "unconnected-(J16-Pad2)") (class "Default")
      (node (ref "J16") (pin "2") (pinfunction "2_2") (pintype "passive"))
    )
    (net (code "87") (name "unconnected-(J16-Pad3)") (class "Default")
      (node (ref "J16") (pin "3") (pinfunction "3_3") (pintype "passive"))
    )
    (net (code "88") (name "unconnected-(J17-Pad1)") (class "Default")
      (node (ref "J17") (pin "1") (pinfunction "1_1") (pintype "passive"))
    )
    (net (code "89") (name "unconnected-(J17-Pad2)") (class "Default")
      (node (ref "J17") (pin "2") (pinfunction "2_2") (pintype "passive"))
    )
    (net (code "90") (name "unconnected-(J17-Pad3)") (class "Default")
      (node (ref "J17") (pin "3") (pinfunction "3_3") (pintype "passive"))
    )
    (net (code "91") (name "unconnected-(J18-Pad1)") (class "Default")
      (node (ref "J18") (pin "1") (pinfunction "1_1") (pintype "passive"))
    )
    (net (code "92") (name "unconnected-(J18-Pad2)") (class "Default")
      (node (ref "J18") (pin "2") (pinfunction "2_2") (pintype "passive"))
    )
    (net (code "93") (name "unconnected-(J18-Pad3)") (class "Default")
      (node (ref "J18") (pin "3") (pinfunction "3_3") (pintype "passive"))
    )
    (net (code "94") (name "unconnected-(J19-Pad8)") (class "Default")
      (node (ref "J19") (pin "8") (pinfunction "8_8") (pintype "passive"))
    )
    (net (code "95") (name "unconnected-(J19-Pad11)") (class "Default")
      (node (ref "J19") (pin "11") (pinfunction "11_11") (pintype "passive"))
    )
    (net (code "96") (name "unconnected-(J19-Pad12)") (class "Default")
      (node (ref "J19") (pin "12") (pinfunction "12_12") (pintype "passive"))
    )
  )
)
